# coil_if.net
KiCad netlist of a schematic drawn in Altium Designer
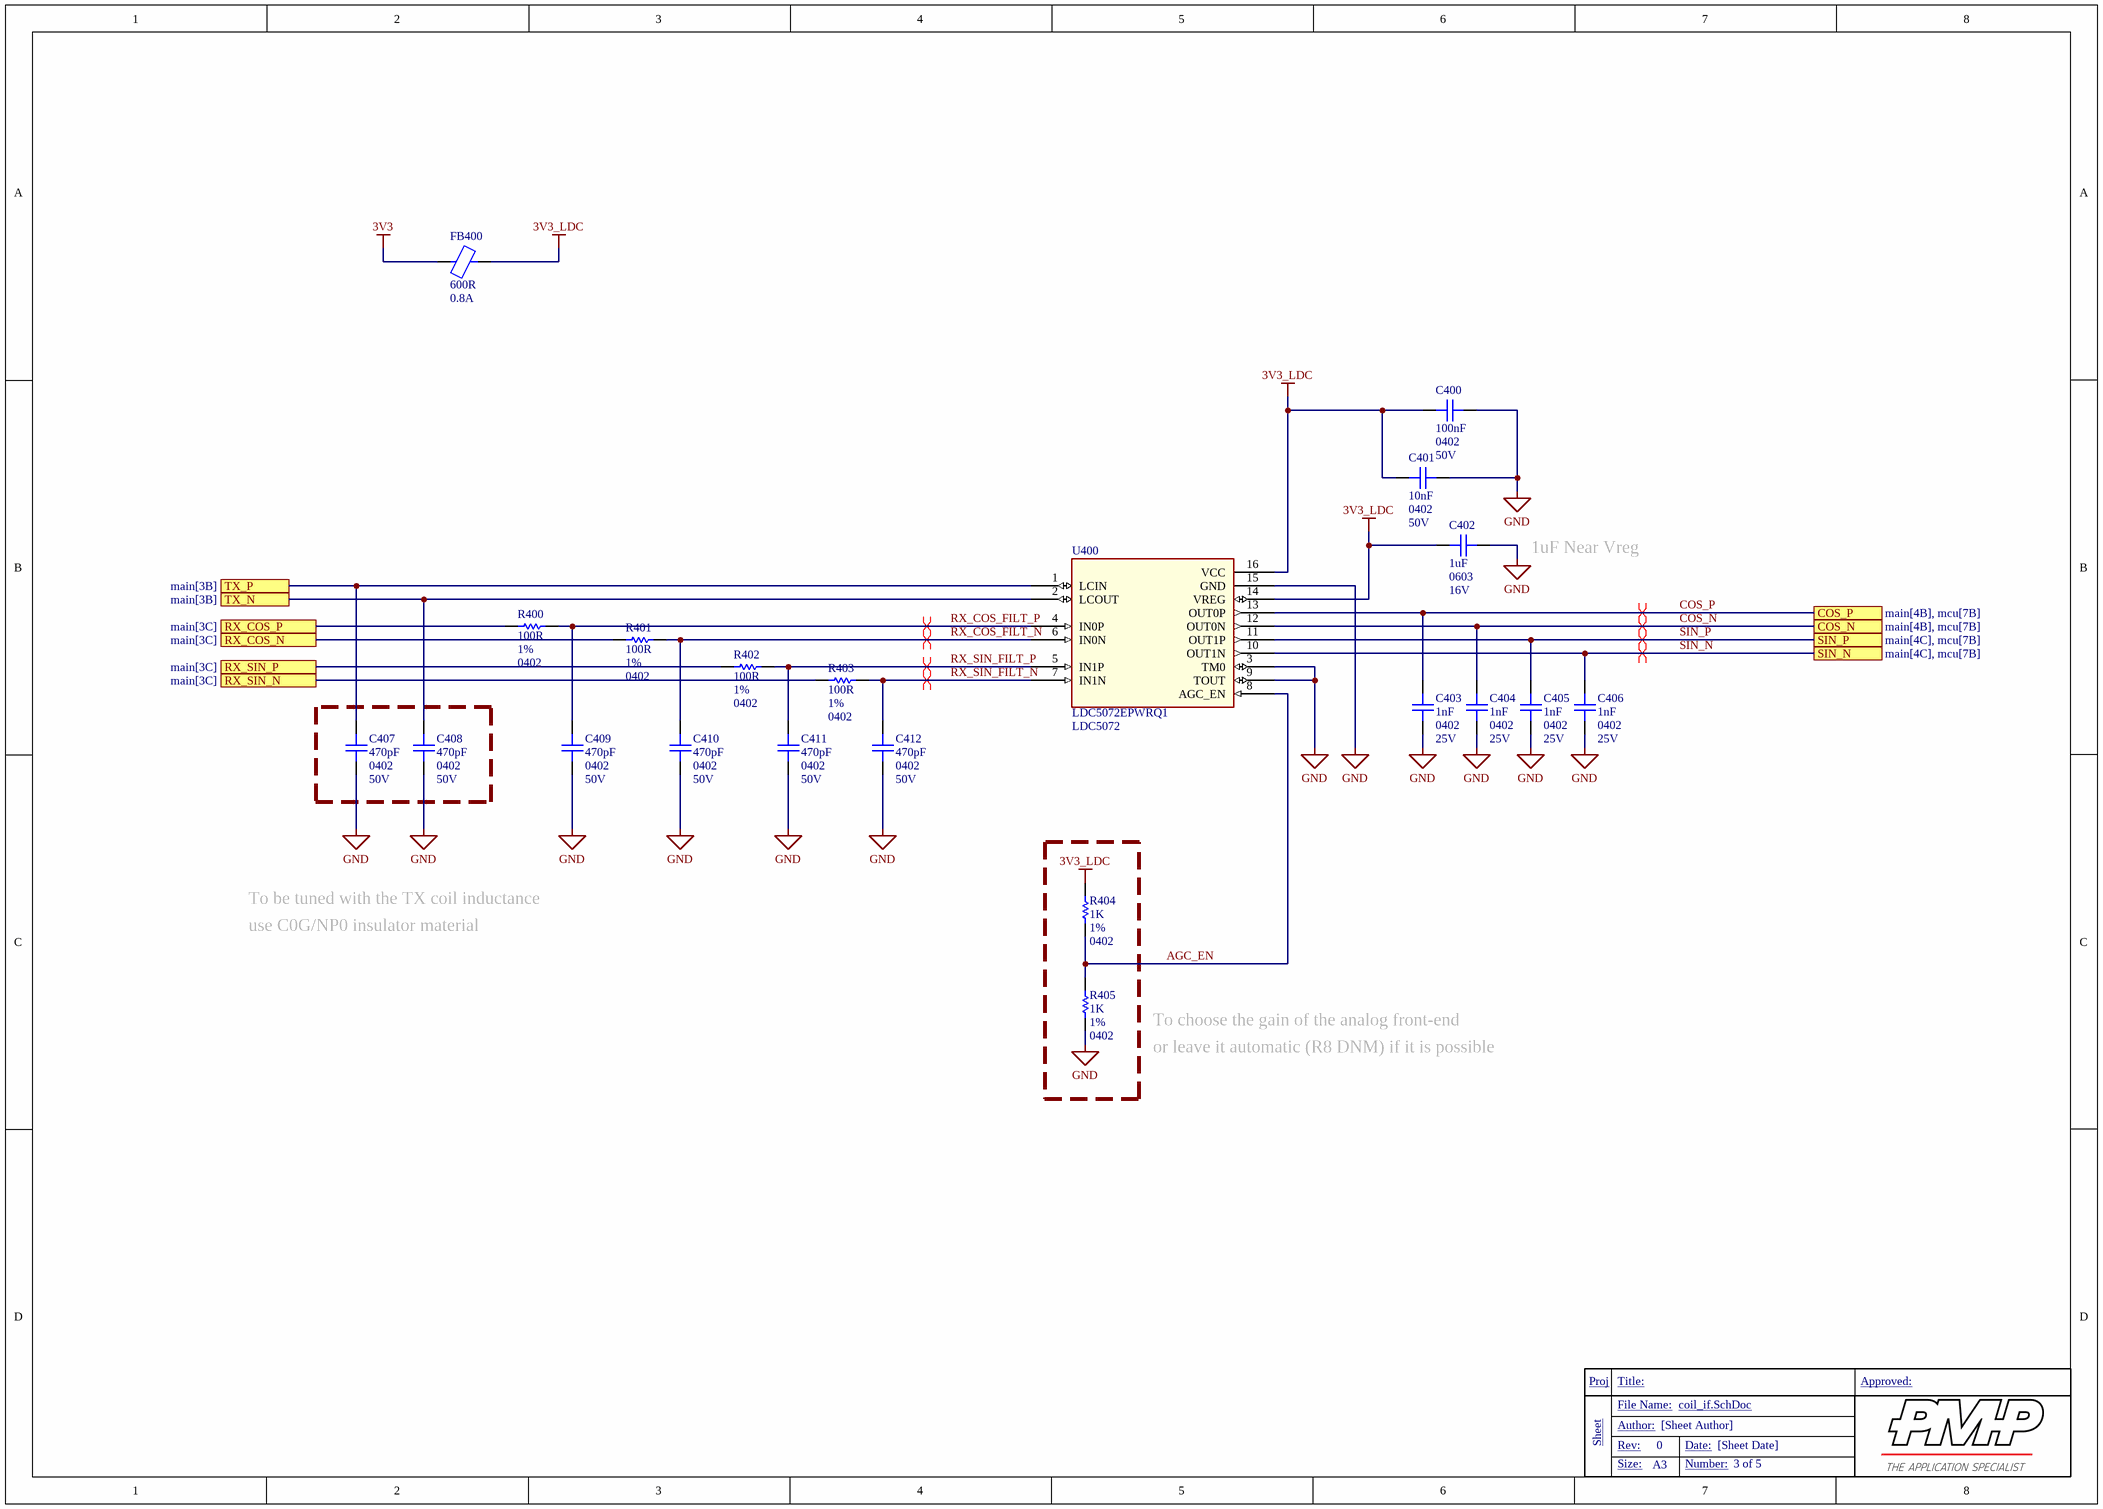
[diagram p0: coil_if.SchDoc]

(export (version "E")
  (design (tool "Eeschema 10.0.6"))
  (components
    (comp (ref "C400")
      (value "100nF")
      (footprint "CER0402")
      (description "MLCC Automotive, 100nF, 0402, 50V, 10%, X7r")
      (fields
        (field (name "CASE/PACKAGE") "0402")
        (field (name "OP VOLTAGE") "50V")
        (field (name "TOLERANCE") "10%")
      )
      (libsource (lib "PMP_CapsDB") (part "CapCer_SMD_2"))
    )
    (comp (ref "C401")
      (value "10nF")
      (footprint "CER0402")
      (description "MLCC Automotive, 10nF, 0402, 25V, 10%, X7r")
      (fields
        (field (name "CASE/PACKAGE") "0402")
        (field (name "OP VOLTAGE") "50V")
        (field (name "TOLERANCE") "10%")
      )
      (libsource (lib "PMP_CapsDB") (part "CapCer_SMD_2"))
    )
    (comp (ref "C402")
      (value "1uF")
      (footprint "CER0603")
      (description "MLCC Automotive, 1uF, 0603, 16V, 10%, X7R")
      (fields
        (field (name "CASE/PACKAGE") "0603")
        (field (name "OP VOLTAGE") "16V")
        (field (name "TOLERANCE") "10%")
      )
      (libsource (lib "PMP_CapsDB") (part "CapCer_SMD_2"))
    )
    (comp (ref "C403")
      (value "1nF")
      (footprint "CER0402")
      (description "MLCC Automotive, 1nF, 0402, 25V, 10%, COG")
      (fields
        (field (name "CASE/PACKAGE") "0402")
        (field (name "OP VOLTAGE") "25V")
        (field (name "TOLERANCE") "5%")
      )
      (libsource (lib "PMP_CapsDB") (part "CapCer_SMD_2"))
    )
    (comp (ref "C404")
      (value "1nF")
      (footprint "CER0402")
      (description "MLCC Automotive, 1nF, 0402, 25V, 10%, COG")
      (fields
        (field (name "CASE/PACKAGE") "0402")
        (field (name "OP VOLTAGE") "25V")
        (field (name "TOLERANCE") "5%")
      )
      (libsource (lib "PMP_CapsDB") (part "CapCer_SMD_2"))
    )
    (comp (ref "C405")
      (value "1nF")
      (footprint "CER0402")
      (description "MLCC Automotive, 1nF, 0402, 25V, 10%, COG")
      (fields
        (field (name "CASE/PACKAGE") "0402")
        (field (name "OP VOLTAGE") "25V")
        (field (name "TOLERANCE") "5%")
      )
      (libsource (lib "PMP_CapsDB") (part "CapCer_SMD_2"))
    )
    (comp (ref "C406")
      (value "1nF")
      (footprint "CER0402")
      (description "MLCC Automotive, 1nF, 0402, 25V, 10%, COG")
      (fields
        (field (name "CASE/PACKAGE") "0402")
        (field (name "OP VOLTAGE") "25V")
        (field (name "TOLERANCE") "5%")
      )
      (libsource (lib "PMP_CapsDB") (part "CapCer_SMD_2"))
    )
    (comp (ref "C407")
      (value "470pF")
      (footprint "CER0402")
      (description "MLCC Automotive, 470pF, 0402, 50V, 5%, COG")
      (fields
        (field (name "CASE/PACKAGE") "0402")
        (field (name "OP VOLTAGE") "50V")
        (field (name "TOLERANCE") "5%")
      )
      (libsource (lib "PMP_CapsDB") (part "CapCer_SMD_2"))
    )
    (comp (ref "C408")
      (value "470pF")
      (footprint "CER0402")
      (description "MLCC Automotive, 470pF, 0402, 50V, 5%, COG")
      (fields
        (field (name "CASE/PACKAGE") "0402")
        (field (name "OP VOLTAGE") "50V")
        (field (name "TOLERANCE") "5%")
      )
      (libsource (lib "PMP_CapsDB") (part "CapCer_SMD_2"))
    )
    (comp (ref "C409")
      (value "470pF")
      (footprint "CER0402")
      (description "MLCC Automotive, 470pF, 0402, 50V, 5%, COG")
      (fields
        (field (name "CASE/PACKAGE") "0402")
        (field (name "OP VOLTAGE") "50V")
        (field (name "TOLERANCE") "5%")
      )
      (libsource (lib "PMP_CapsDB") (part "CapCer_SMD_2"))
    )
    (comp (ref "C410")
      (value "470pF")
      (footprint "CER0402")
      (description "MLCC Automotive, 470pF, 0402, 50V, 5%, COG")
      (fields
        (field (name "CASE/PACKAGE") "0402")
        (field (name "OP VOLTAGE") "50V")
        (field (name "TOLERANCE") "5%")
      )
      (libsource (lib "PMP_CapsDB") (part "CapCer_SMD_2"))
    )
    (comp (ref "C411")
      (value "470pF")
      (footprint "CER0402")
      (description "MLCC Automotive, 470pF, 0402, 50V, 5%, COG")
      (fields
        (field (name "CASE/PACKAGE") "0402")
        (field (name "OP VOLTAGE") "50V")
        (field (name "TOLERANCE") "5%")
      )
      (libsource (lib "PMP_CapsDB") (part "CapCer_SMD_2"))
    )
    (comp (ref "C412")
      (value "470pF")
      (footprint "CER0402")
      (description "MLCC Automotive, 470pF, 0402, 50V, 5%, COG")
      (fields
        (field (name "CASE/PACKAGE") "0402")
        (field (name "OP VOLTAGE") "50V")
        (field (name "TOLERANCE") "5%")
      )
      (libsource (lib "PMP_CapsDB") (part "CapCer_SMD_2"))
    )
    (comp (ref "FB400")
      (value "~")
      (footprint "FEB0603")
      (description "SMD EMI Suppression Ferrite Bead 600R, 0603, For DC Power")
      (fields (field (name "IMPEDENCE @100MHZ") "600R") (field (name "RATED CURRENT @85°C") "0.8A"))
      (libsource (lib "PMP_FerriteDB") (part "FER_SMD_2_Ferrite_Bead"))
    )
    (comp (ref "R400")
      (value "100R")
      (footprint "Res0402")
      (description "Thick Film SM Chip Resistors, 100R, 0402, ±1%, 1/16W")
      (fields
        (field (name "TOLERANCE") "1%")
        (field (name "CASE/PACKAGE") "0402")
        (field (name "POWER") "63mW")
        (field (name "Comment") "SMD Resistor")
      )
      (libsource (lib "PMP_ResDB") (part "Res_SMD_2"))
    )
    (comp (ref "R401")
      (value "100R")
      (footprint "Res0402")
      (description "Thick Film SM Chip Resistors, 100R, 0402, ±1%, 1/16W")
      (fields
        (field (name "TOLERANCE") "1%")
        (field (name "CASE/PACKAGE") "0402")
        (field (name "POWER") "63mW")
        (field (name "Comment") "SMD Resistor")
      )
      (libsource (lib "PMP_ResDB") (part "Res_SMD_2"))
    )
    (comp (ref "R402")
      (value "100R")
      (footprint "Res0402")
      (description "Thick Film SM Chip Resistors, 100R, 0402, ±1%, 1/16W")
      (fields
        (field (name "TOLERANCE") "1%")
        (field (name "CASE/PACKAGE") "0402")
        (field (name "POWER") "63mW")
        (field (name "Comment") "SMD Resistor")
      )
      (libsource (lib "PMP_ResDB") (part "Res_SMD_2"))
    )
    (comp (ref "R403")
      (value "100R")
      (footprint "Res0402")
      (description "Thick Film SM Chip Resistors, 100R, 0402, ±1%, 1/16W")
      (fields
        (field (name "TOLERANCE") "1%")
        (field (name "CASE/PACKAGE") "0402")
        (field (name "POWER") "63mW")
        (field (name "Comment") "SMD Resistor")
      )
      (libsource (lib "PMP_ResDB") (part "Res_SMD_2"))
    )
    (comp (ref "R404")
      (value "1K")
      (footprint "Res0402")
      (description "Thick Film SM Chip Resistors, 1K, 0402, ±1%, 1/16W")
      (fields
        (field (name "TOLERANCE") "1%")
        (field (name "CASE/PACKAGE") "0402")
        (field (name "POWER") "63mW")
        (field (name "Comment") "SMD Resistor")
      )
      (libsource (lib "PMP_ResDB") (part "Res_SMD_2"))
    )
    (comp (ref "R405")
      (value "1K")
      (footprint "Res0402")
      (description "Thick Film SM Chip Resistors, 1K, 0402, ±1%, 1/16W")
      (fields
        (field (name "TOLERANCE") "1%")
        (field (name "CASE/PACKAGE") "0402")
        (field (name "POWER") "63mW")
        (field (name "Comment") "SMD Resistor")
      )
      (libsource (lib "PMP_ResDB") (part "Res_SMD_2"))
    )
    (comp (ref "U400")
      (value "LDC5072EPWRQ1")
      (footprint "TSSOP16-PW_TEX")
      (description "IPS interface IC")
      (fields
        (field (name "ALTIUM_VALUE") "LDC5072")
        (field (name "COPYRIGHT") "Copyright (C) 2026 Ultra Librarian. All rights reserved.")
      )
      (libsource (lib "PMP_ICsDB") (part "TI_LDC5072EPWRQ1"))
    )
  )
  (nets
    (net (code "1") (name "/AGC_EN") (class "Default")
      (node (ref "R404") (pin "1") (pinfunction "1_1") (pintype "passive"))
      (node (ref "R405") (pin "2") (pinfunction "2_2") (pintype "passive"))
      (node (ref "U400") (pin "8") (pinfunction "AGC_EN_8") (pintype "input"))
    )
    (net (code "2") (name "/COS_N") (class "Default")
      (node (ref "C404") (pin "1") (pinfunction "1_1") (pintype "passive"))
      (node (ref "U400") (pin "12") (pinfunction "OUT0N_12") (pintype "output"))
    )
    (net (code "3") (name "/COS_P") (class "Default")
      (node (ref "C403") (pin "1") (pinfunction "1_1") (pintype "passive"))
      (node (ref "U400") (pin "13") (pinfunction "OUT0P_13") (pintype "output"))
    )
    (net (code "4") (name "/RX_COS_FILT_N") (class "Default")
      (node (ref "C410") (pin "1") (pinfunction "1_1") (pintype "passive"))
      (node (ref "R401") (pin "2") (pinfunction "2_2") (pintype "passive"))
      (node (ref "U400") (pin "6") (pinfunction "IN0N_6") (pintype "input"))
    )
    (net (code "5") (name "/RX_COS_FILT_P") (class "Default")
      (node (ref "C409") (pin "1") (pinfunction "1_1") (pintype "passive"))
      (node (ref "R400") (pin "2") (pinfunction "2_2") (pintype "passive"))
      (node (ref "U400") (pin "4") (pinfunction "IN0P_4") (pintype "input"))
    )
    (net (code "6") (name "/RX_COS_N") (class "Default")
      (node (ref "R401") (pin "1") (pinfunction "1_1") (pintype "passive"))
    )
    (net (code "7") (name "/RX_COS_P") (class "Default")
      (node (ref "R400") (pin "1") (pinfunction "1_1") (pintype "passive"))
    )
    (net (code "8") (name "/RX_SIN_FILT_N") (class "Default")
      (node (ref "C412") (pin "1") (pinfunction "1_1") (pintype "passive"))
      (node (ref "R403") (pin "2") (pinfunction "2_2") (pintype "passive"))
      (node (ref "U400") (pin "7") (pinfunction "IN1N_7") (pintype "input"))
    )
    (net (code "9") (name "/RX_SIN_FILT_P") (class "Default")
      (node (ref "C411") (pin "1") (pinfunction "1_1") (pintype "passive"))
      (node (ref "R402") (pin "2") (pinfunction "2_2") (pintype "passive"))
      (node (ref "U400") (pin "5") (pinfunction "IN1P_5") (pintype "input"))
    )
    (net (code "10") (name "/RX_SIN_N") (class "Default")
      (node (ref "R403") (pin "1") (pinfunction "1_1") (pintype "passive"))
    )
    (net (code "11") (name "/RX_SIN_P") (class "Default")
      (node (ref "R402") (pin "1") (pinfunction "1_1") (pintype "passive"))
    )
    (net (code "12") (name "/SIN_N") (class "Default")
      (node (ref "C406") (pin "1") (pinfunction "1_1") (pintype "passive"))
      (node (ref "U400") (pin "10") (pinfunction "OUT1N_10") (pintype "output"))
    )
    (net (code "13") (name "/SIN_P") (class "Default")
      (node (ref "C405") (pin "1") (pinfunction "1_1") (pintype "passive"))
      (node (ref "U400") (pin "11") (pinfunction "OUT1P_11") (pintype "output"))
    )
    (net (code "14") (name "/TX_N") (class "Default")
      (node (ref "C408") (pin "1") (pinfunction "1_1") (pintype "passive"))
      (node (ref "U400") (pin "2") (pinfunction "LCOUT_2") (pintype "bidirectional"))
    )
    (net (code "15") (name "/TX_P") (class "Default")
      (node (ref "C407") (pin "1") (pinfunction "1_1") (pintype "passive"))
      (node (ref "U400") (pin "1") (pinfunction "LCIN_1") (pintype "bidirectional"))
    )
    (net (code "16") (name "3V3") (class "Default")
      (node (ref "FB400") (pin "1") (pinfunction "1_1") (pintype "passive"))
    )
    (net (code "17") (name "3V3_LDC") (class "Default")
      (node (ref "C400") (pin "1") (pinfunction "1_1") (pintype "passive"))
      (node (ref "C401") (pin "1") (pinfunction "1_1") (pintype "passive"))
      (node (ref "C402") (pin "1") (pinfunction "1_1") (pintype "passive"))
      (node (ref "FB400") (pin "2") (pinfunction "2_2") (pintype "passive"))
      (node (ref "R404") (pin "2") (pinfunction "2_2") (pintype "passive"))
      (node (ref "U400") (pin "14") (pinfunction "VREG_14") (pintype "bidirectional"))
      (node (ref "U400") (pin "16") (pinfunction "VCC_16") (pintype "power_in"))
    )
    (net (code "18") (name "GND") (class "Default")
      (node (ref "C400") (pin "2") (pinfunction "2_2") (pintype "passive"))
      (node (ref "C401") (pin "2") (pinfunction "2_2") (pintype "passive"))
      (node (ref "C402") (pin "2") (pinfunction "2_2") (pintype "passive"))
      (node (ref "C403") (pin "2") (pinfunction "2_2") (pintype "passive"))
      (node (ref "C404") (pin "2") (pinfunction "2_2") (pintype "passive"))
      (node (ref "C405") (pin "2") (pinfunction "2_2") (pintype "passive"))
      (node (ref "C406") (pin "2") (pinfunction "2_2") (pintype "passive"))
      (node (ref "C407") (pin "2") (pinfunction "2_2") (pintype "passive"))
      (node (ref "C408") (pin "2") (pinfunction "2_2") (pintype "passive"))
      (node (ref "C409") (pin "2") (pinfunction "2_2") (pintype "passive"))
      (node (ref "C410") (pin "2") (pinfunction "2_2") (pintype "passive"))
      (node (ref "C411") (pin "2") (pinfunction "2_2") (pintype "passive"))
      (node (ref "C412") (pin "2") (pinfunction "2_2") (pintype "passive"))
      (node (ref "R405") (pin "1") (pinfunction "1_1") (pintype "passive"))
      (node (ref "U400") (pin "15") (pinfunction "GND_15") (pintype "power_in"))
      (node (ref "U400") (pin "3") (pinfunction "TM0_3") (pintype "bidirectional"))
      (node (ref "U400") (pin "9") (pinfunction "TOUT_9") (pintype "bidirectional"))
    )
  )
)
